# canbus_shield-v1.net
KiCad netlist of a schematic drawn in EAGLE
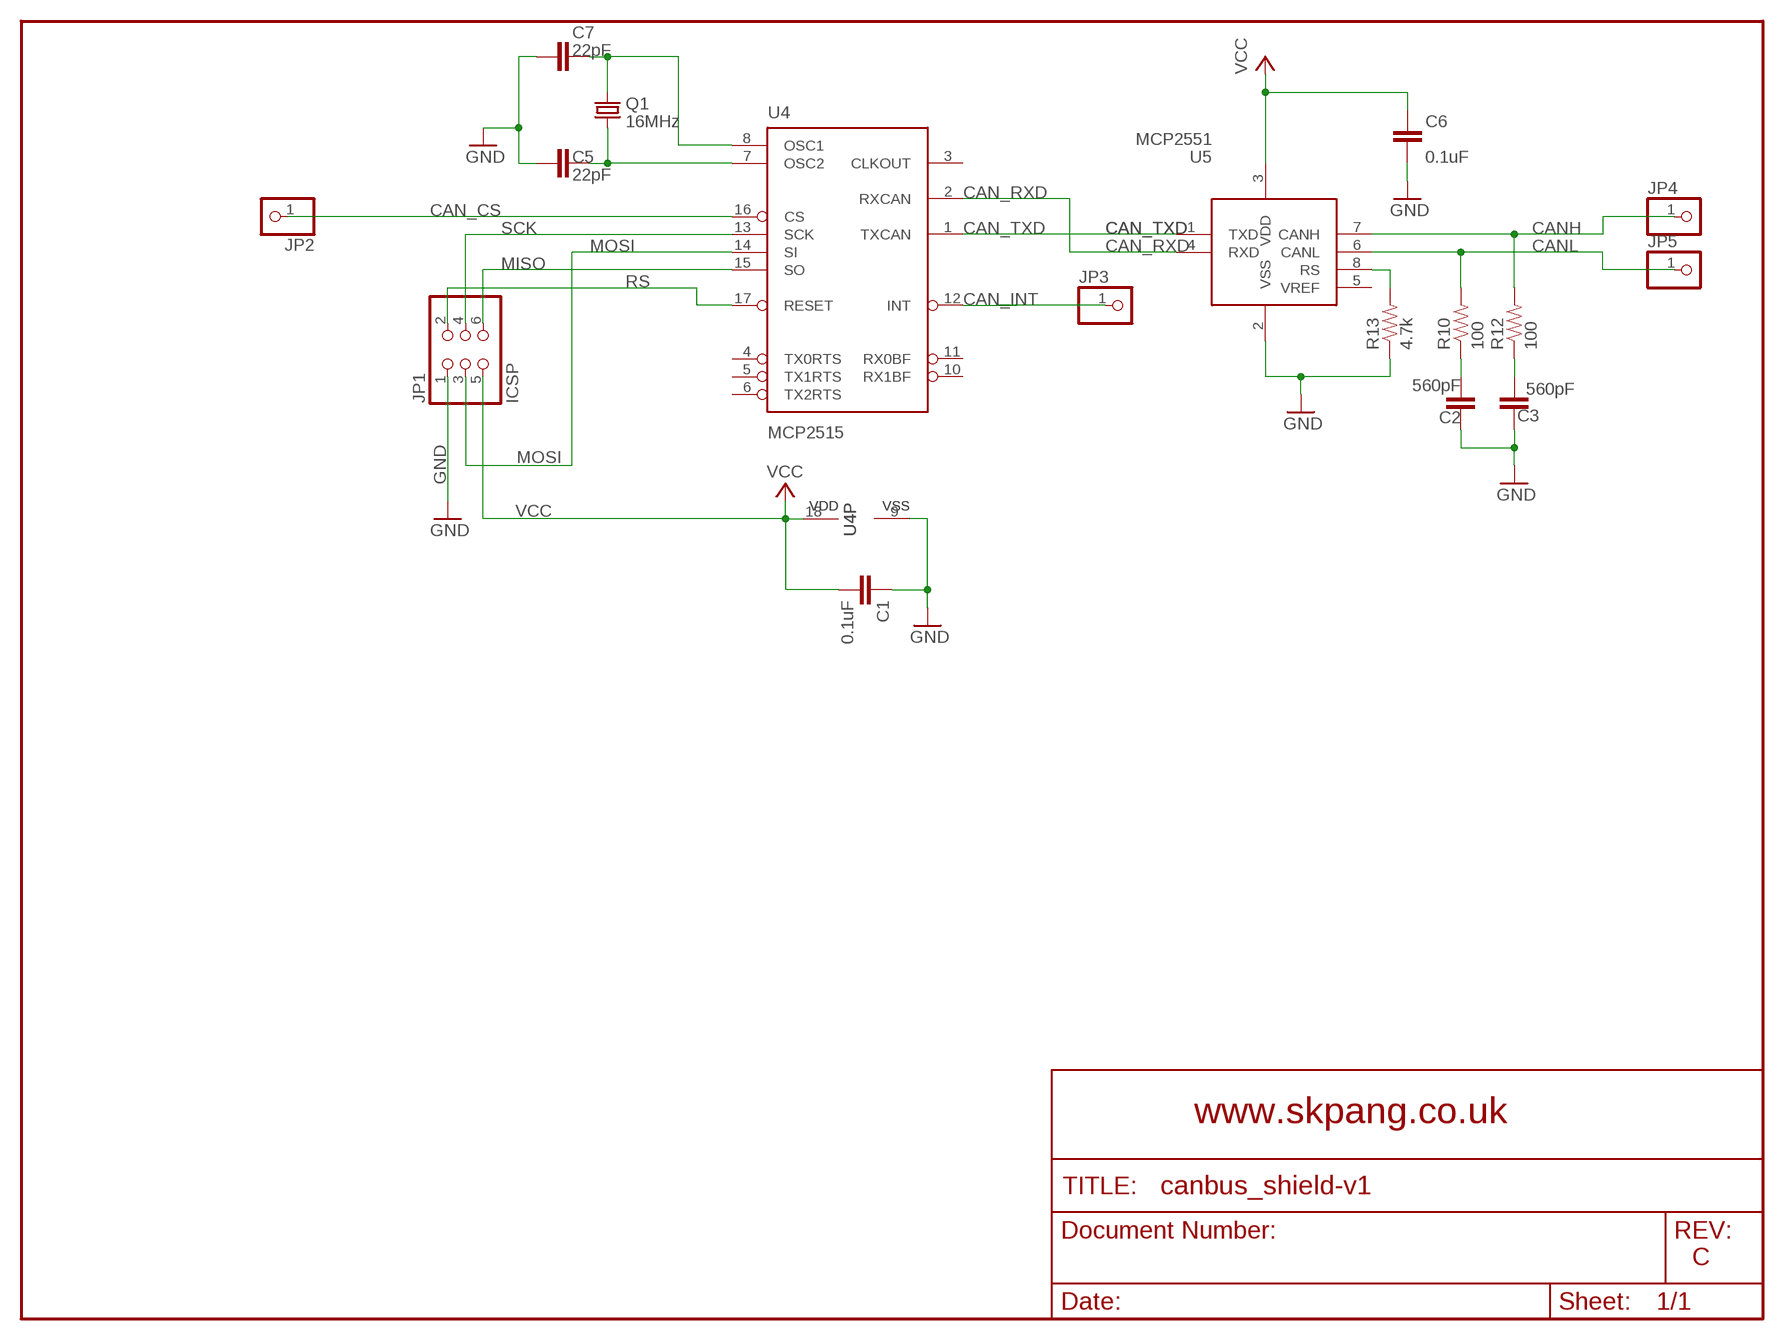
[diagram p0: schematic, sheet 1]

(export (version "E")
  (design (tool "Eeschema 10.0.6"))
  (components
    (comp (ref "C1")
      (value "0.1uF")
      (footprint "eagle-import:0603-CAP")
      (libsource (lib "eagle-import") (part "CAP0603-CAP"))
    )
    (comp (ref "C2")
      (value "560pF")
      (footprint "eagle-import:0603-CAP")
      (libsource (lib "eagle-import") (part "CAP0603-CAP"))
    )
    (comp (ref "C3")
      (value "560pF")
      (footprint "eagle-import:0603-CAP")
      (libsource (lib "eagle-import") (part "CAP0603-CAP"))
    )
    (comp (ref "C5")
      (value "22pF")
      (footprint "eagle-import:0603-CAP")
      (libsource (lib "eagle-import") (part "CAP0603-CAP"))
    )
    (comp (ref "C6")
      (value "0.1uF")
      (footprint "eagle-import:0603-CAP")
      (libsource (lib "eagle-import") (part "CAP0603-CAP"))
    )
    (comp (ref "C7")
      (value "22pF")
      (footprint "eagle-import:0603-CAP")
      (libsource (lib "eagle-import") (part "CAP0603-CAP"))
    )
    (comp (ref "JP1")
      (value "ICSP")
      (footprint "eagle-import:2X03")
      (libsource (lib "eagle-import") (part "PINHD-2X3"))
    )
    (comp (ref "JP2")
      (value "PINHD-1X1")
      (footprint "eagle-import:1X01")
      (libsource (lib "eagle-import") (part "PINHD-1X1"))
    )
    (comp (ref "JP3")
      (value "PINHD-1X1")
      (footprint "eagle-import:1X01")
      (libsource (lib "eagle-import") (part "PINHD-1X1"))
    )
    (comp (ref "JP4")
      (value "PINHD-1X1")
      (footprint "eagle-import:1X01")
      (libsource (lib "eagle-import") (part "PINHD-1X1"))
    )
    (comp (ref "JP5")
      (value "PINHD-1X1")
      (footprint "eagle-import:1X01")
      (libsource (lib "eagle-import") (part "PINHD-1X1"))
    )
    (comp (ref "Q1")
      (value "16MHz")
      (footprint "eagle-import:CRYSTAL-SMD-5X3")
      (libsource (lib "eagle-import") (part "CRYSTAL5X3"))
    )
    (comp (ref "R10")
      (value "100")
      (footprint "eagle-import:0603-RES")
      (libsource (lib "eagle-import") (part "RESISTOR0603-RES"))
    )
    (comp (ref "R12")
      (value "100")
      (footprint "eagle-import:0603-RES")
      (libsource (lib "eagle-import") (part "RESISTOR0603-RES"))
    )
    (comp (ref "R13")
      (value "4.7k")
      (footprint "eagle-import:0603-RES")
      (libsource (lib "eagle-import") (part "RESISTOR0603-RES"))
    )
    (comp (ref "U4")
      (value "MCP2515")
      (footprint "eagle-import:SO-18W")
      (libsource (lib "eagle-import") (part "MCP2510SO"))
    )
    (comp (ref "U5")
      (value "MCP2551")
      (footprint "eagle-import:SO-08M")
      (libsource (lib "eagle-import") (part "MCP2551"))
    )
  )
  (nets
    (net (code "1") (name "/CANH") (class "Default")
      (node (ref "JP4") (pin "1") (pinfunction "1_1") (pintype "passive"))
      (node (ref "R12") (pin "2") (pinfunction "2_2") (pintype "passive"))
      (node (ref "U5") (pin "7") (pinfunction "CANH_7") (pintype "bidirectional"))
    )
    (net (code "2") (name "/CANL") (class "Default")
      (node (ref "JP5") (pin "1") (pinfunction "1_1") (pintype "passive"))
      (node (ref "R10") (pin "2") (pinfunction "2_2") (pintype "passive"))
      (node (ref "U5") (pin "6") (pinfunction "CANL_6") (pintype "bidirectional"))
    )
    (net (code "3") (name "/CAN_CS") (class "Default")
      (node (ref "JP2") (pin "1") (pinfunction "1_1") (pintype "passive"))
      (node (ref "U4") (pin "16") (pinfunction "CS_16") (pintype "input"))
    )
    (net (code "4") (name "/CAN_INT") (class "Default")
      (node (ref "JP3") (pin "1") (pinfunction "1_1") (pintype "passive"))
      (node (ref "U4") (pin "12") (pinfunction "INT_12") (pintype "output"))
    )
    (net (code "5") (name "/CAN_RXD") (class "Default")
      (node (ref "U4") (pin "2") (pinfunction "RXCAN_2") (pintype "input"))
      (node (ref "U5") (pin "4") (pinfunction "RXD_4") (pintype "bidirectional"))
    )
    (net (code "6") (name "/CAN_TXD") (class "Default")
      (node (ref "U4") (pin "1") (pinfunction "TXCAN_1") (pintype "output"))
      (node (ref "U5") (pin "1") (pinfunction "TXD_1") (pintype "bidirectional"))
    )
    (net (code "7") (name "/MISO") (class "Default")
      (node (ref "JP1") (pin "6") (pinfunction "6_6") (pintype "passive"))
      (node (ref "U4") (pin "15") (pinfunction "SO_15") (pintype "output"))
    )
    (net (code "8") (name "/MOSI") (class "Default")
      (node (ref "JP1") (pin "3") (pinfunction "3_3") (pintype "passive"))
      (node (ref "U4") (pin "14") (pinfunction "SI_14") (pintype "input"))
    )
    (net (code "9") (name "/RS") (class "Default")
      (node (ref "JP1") (pin "2") (pinfunction "2_2") (pintype "passive"))
      (node (ref "U4") (pin "17") (pinfunction "RESET_17") (pintype "input"))
    )
    (net (code "10") (name "/SCK") (class "Default")
      (node (ref "JP1") (pin "4") (pinfunction "4_4") (pintype "passive"))
      (node (ref "U4") (pin "13") (pinfunction "SCK_13") (pintype "input"))
    )
    (net (code "11") (name "GND") (class "Default")
      (node (ref "C1") (pin "1") (pinfunction "1_1") (pintype "passive"))
      (node (ref "C2") (pin "1") (pinfunction "1_1") (pintype "passive"))
      (node (ref "C3") (pin "1") (pinfunction "1_1") (pintype "passive"))
      (node (ref "C5") (pin "1") (pinfunction "1_1") (pintype "passive"))
      (node (ref "C6") (pin "1") (pinfunction "1_1") (pintype "passive"))
      (node (ref "C7") (pin "1") (pinfunction "1_1") (pintype "passive"))
      (node (ref "JP1") (pin "1") (pinfunction "1_1") (pintype "passive"))
      (node (ref "R13") (pin "1") (pinfunction "1_1") (pintype "passive"))
      (node (ref "U4") (pin "9") (pinfunction "VSS_9") (pintype "power_in"))
      (node (ref "U5") (pin "2") (pinfunction "VSS_2") (pintype "power_in"))
    )
    (net (code "12") (name "Net-(C2-Pad2)") (class "Default")
      (node (ref "C2") (pin "2") (pinfunction "2_2") (pintype "passive"))
      (node (ref "R10") (pin "1") (pinfunction "1_1") (pintype "passive"))
    )
    (net (code "13") (name "Net-(C3-Pad2)") (class "Default")
      (node (ref "C3") (pin "2") (pinfunction "2_2") (pintype "passive"))
      (node (ref "R12") (pin "1") (pinfunction "1_1") (pintype "passive"))
    )
    (net (code "14") (name "Net-(Q1-2)") (class "Default")
      (node (ref "C7") (pin "2") (pinfunction "2_2") (pintype "passive"))
      (node (ref "Q1") (pin "3") (pinfunction "2_3") (pintype "passive"))
      (node (ref "U4") (pin "8") (pinfunction "OSC1_8") (pintype "input"))
    )
    (net (code "15") (name "Net-(U4A-OSC2)") (class "Default")
      (node (ref "C5") (pin "2") (pinfunction "2_2") (pintype "passive"))
      (node (ref "Q1") (pin "1") (pinfunction "1_1") (pintype "passive"))
      (node (ref "U4") (pin "7") (pinfunction "OSC2_7") (pintype "output"))
    )
    (net (code "16") (name "Net-(U5-RS)") (class "Default")
      (node (ref "R13") (pin "2") (pinfunction "2_2") (pintype "passive"))
      (node (ref "U5") (pin "8") (pinfunction "RS_8") (pintype "bidirectional"))
    )
    (net (code "17") (name "VCC") (class "Default")
      (node (ref "C1") (pin "2") (pinfunction "2_2") (pintype "passive"))
      (node (ref "C6") (pin "2") (pinfunction "2_2") (pintype "passive"))
      (node (ref "JP1") (pin "5") (pinfunction "5_5") (pintype "passive"))
      (node (ref "U4") (pin "18") (pinfunction "VDD_18") (pintype "power_in"))
      (node (ref "U5") (pin "3") (pinfunction "VDD_3") (pintype "power_in"))
    )
    (net (code "18") (name "unconnected-(U4A-CLKOUT-Pad3)") (class "Default")
      (node (ref "U4") (pin "3") (pinfunction "CLKOUT_3") (pintype "output"))
    )
    (net (code "19") (name "unconnected-(U4A-RX0BF-Pad11)") (class "Default")
      (node (ref "U4") (pin "11") (pinfunction "RX0BF_11") (pintype "output"))
    )
    (net (code "20") (name "unconnected-(U4A-RX1BF-Pad10)") (class "Default")
      (node (ref "U4") (pin "10") (pinfunction "RX1BF_10") (pintype "output"))
    )
    (net (code "21") (name "unconnected-(U4A-TX0RTS-Pad4)") (class "Default")
      (node (ref "U4") (pin "4") (pinfunction "TX0RTS_4") (pintype "input"))
    )
    (net (code "22") (name "unconnected-(U4A-TX1RTS-Pad5)") (class "Default")
      (node (ref "U4") (pin "5") (pinfunction "TX1RTS_5") (pintype "input"))
    )
    (net (code "23") (name "unconnected-(U4A-TX2RTS-Pad6)") (class "Default")
      (node (ref "U4") (pin "6") (pinfunction "TX2RTS_6") (pintype "input"))
    )
    (net (code "24") (name "unconnected-(U5-VREF-Pad5)") (class "Default")
      (node (ref "U5") (pin "5") (pinfunction "VREF_5") (pintype "bidirectional"))
    )
  )
)
